# FPGA_S7.net
KiCad netlist of a schematic drawn in EAGLE
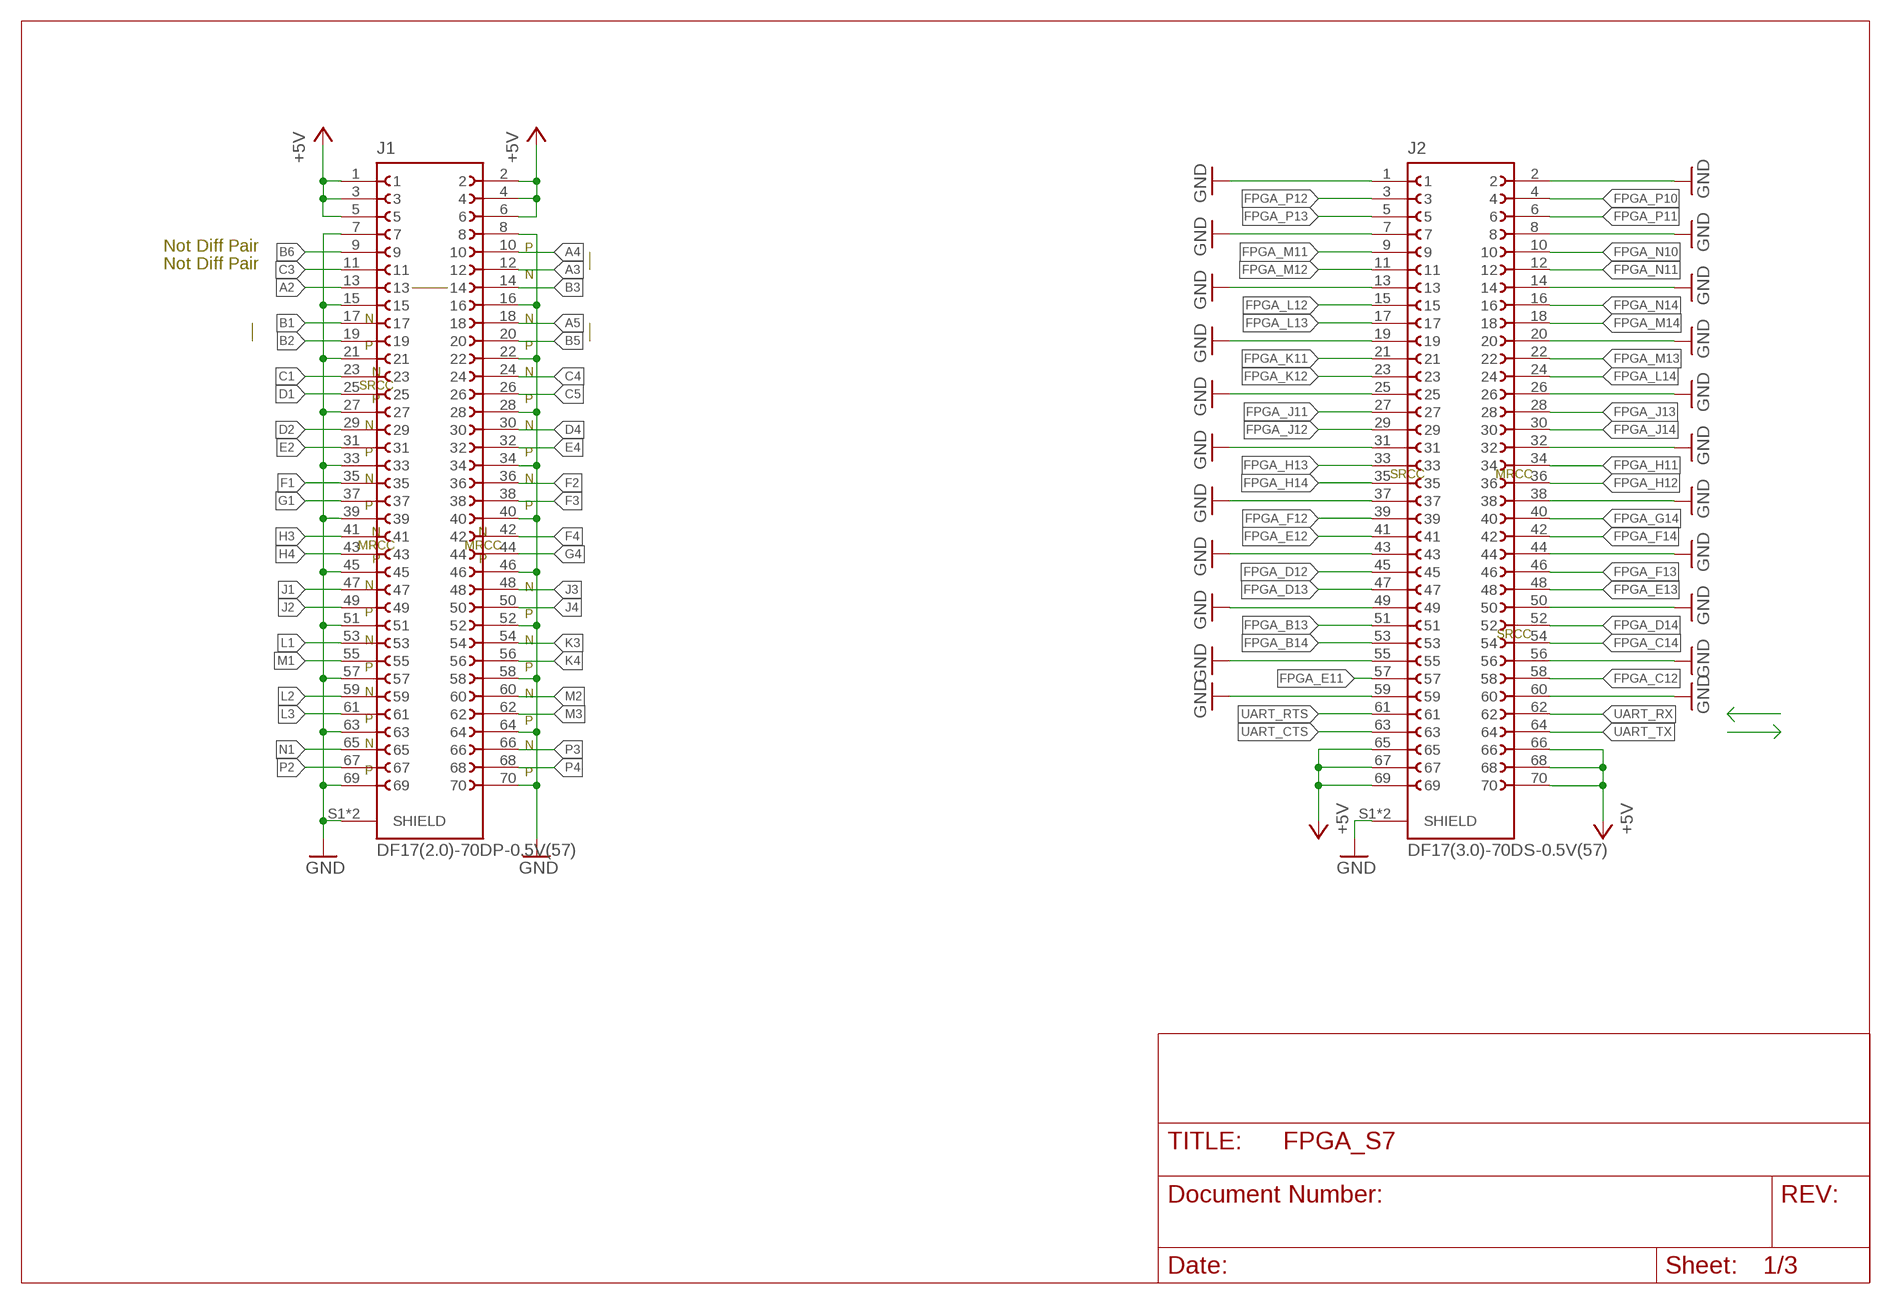
[diagram p0: schematic, sheet 1]
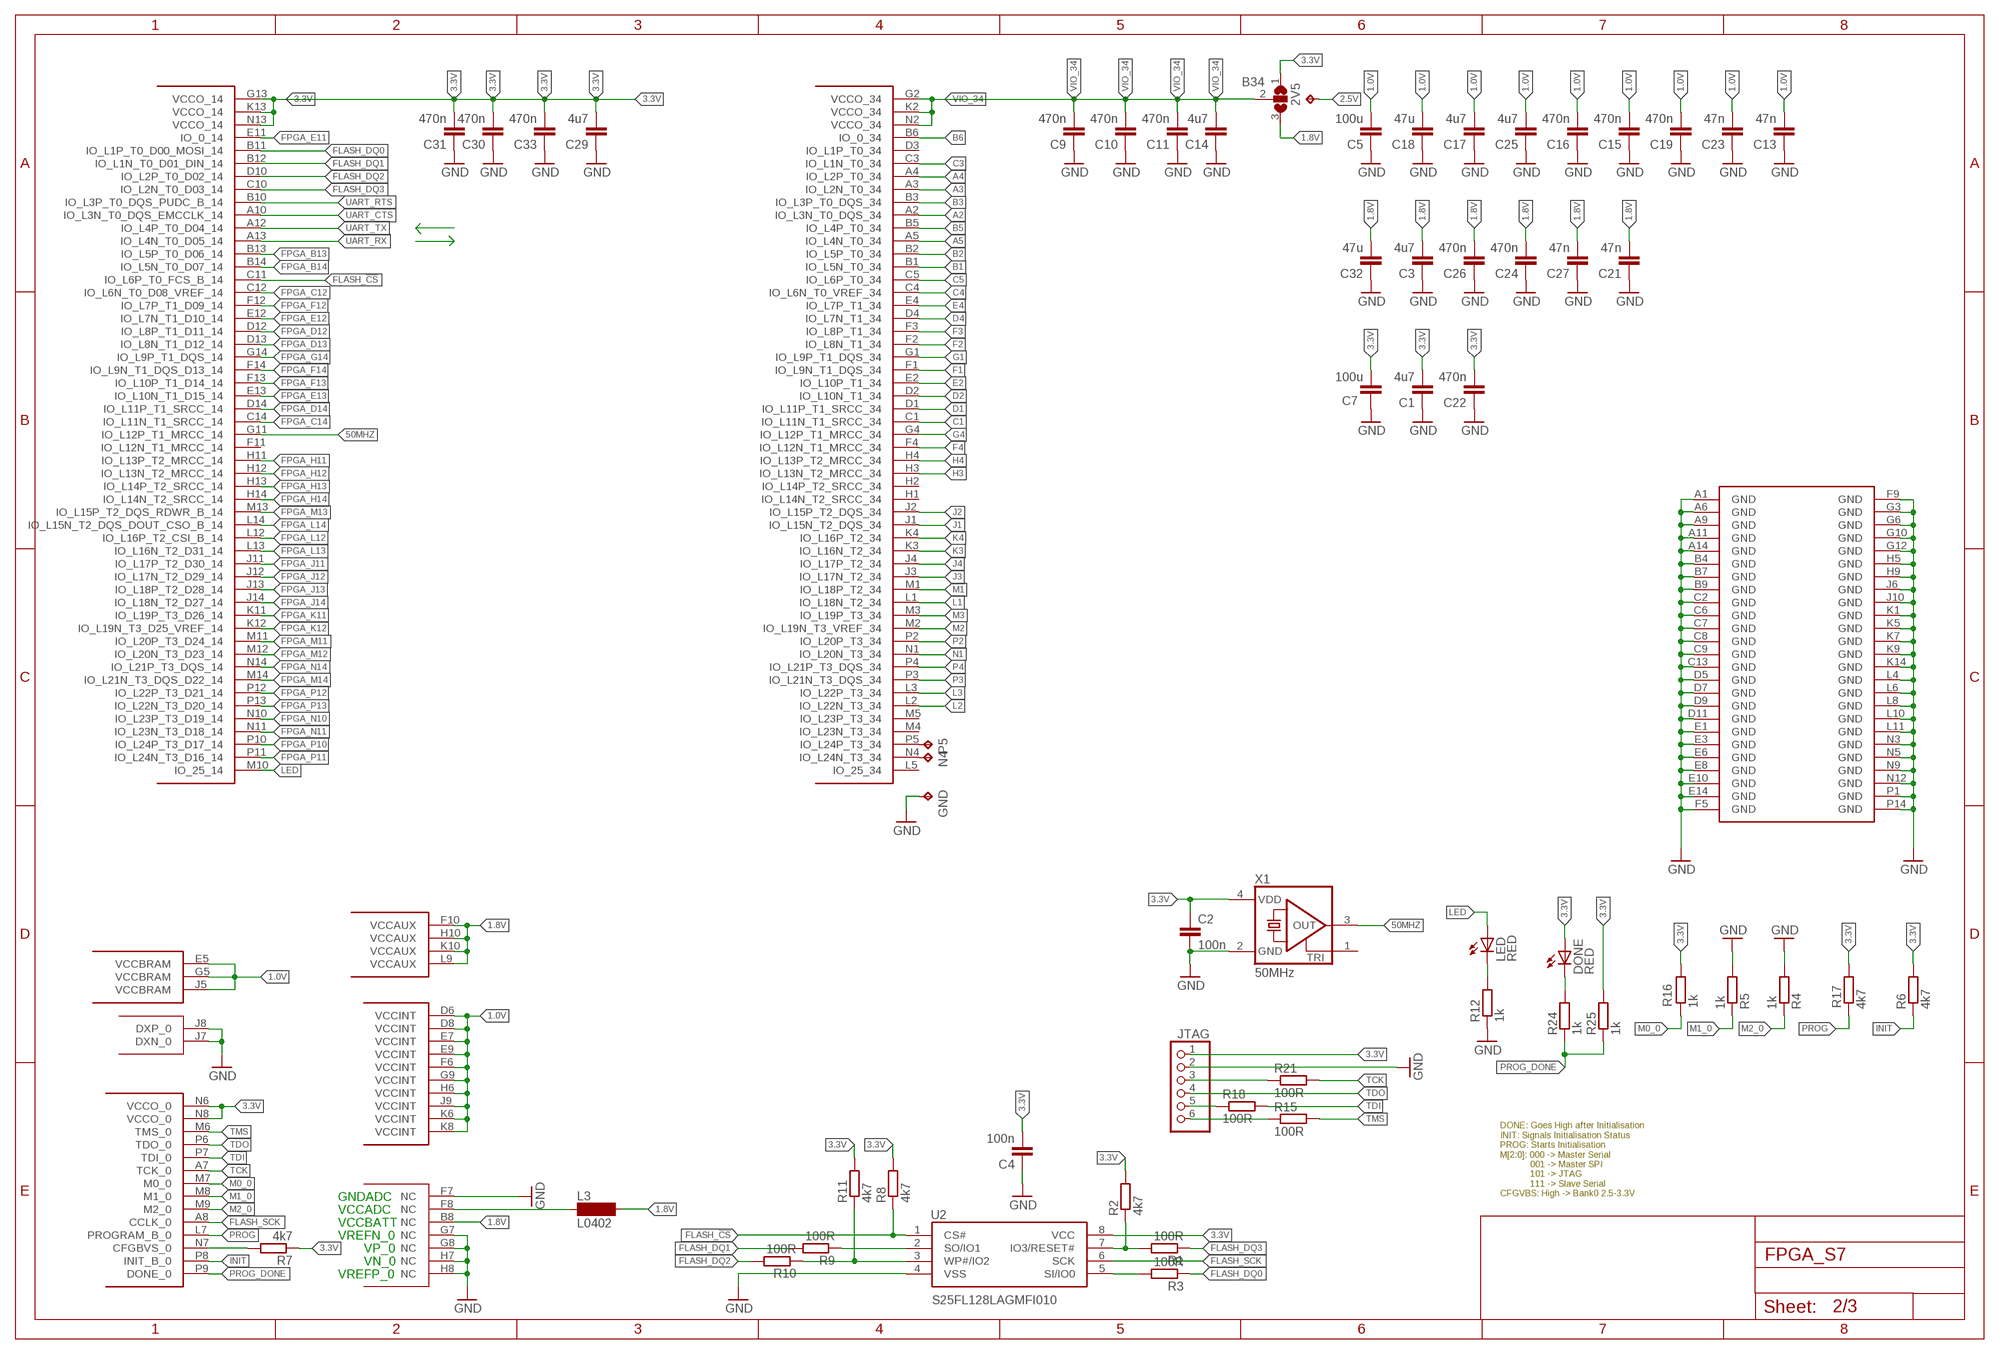
[diagram p1: schematic, sheet 2]
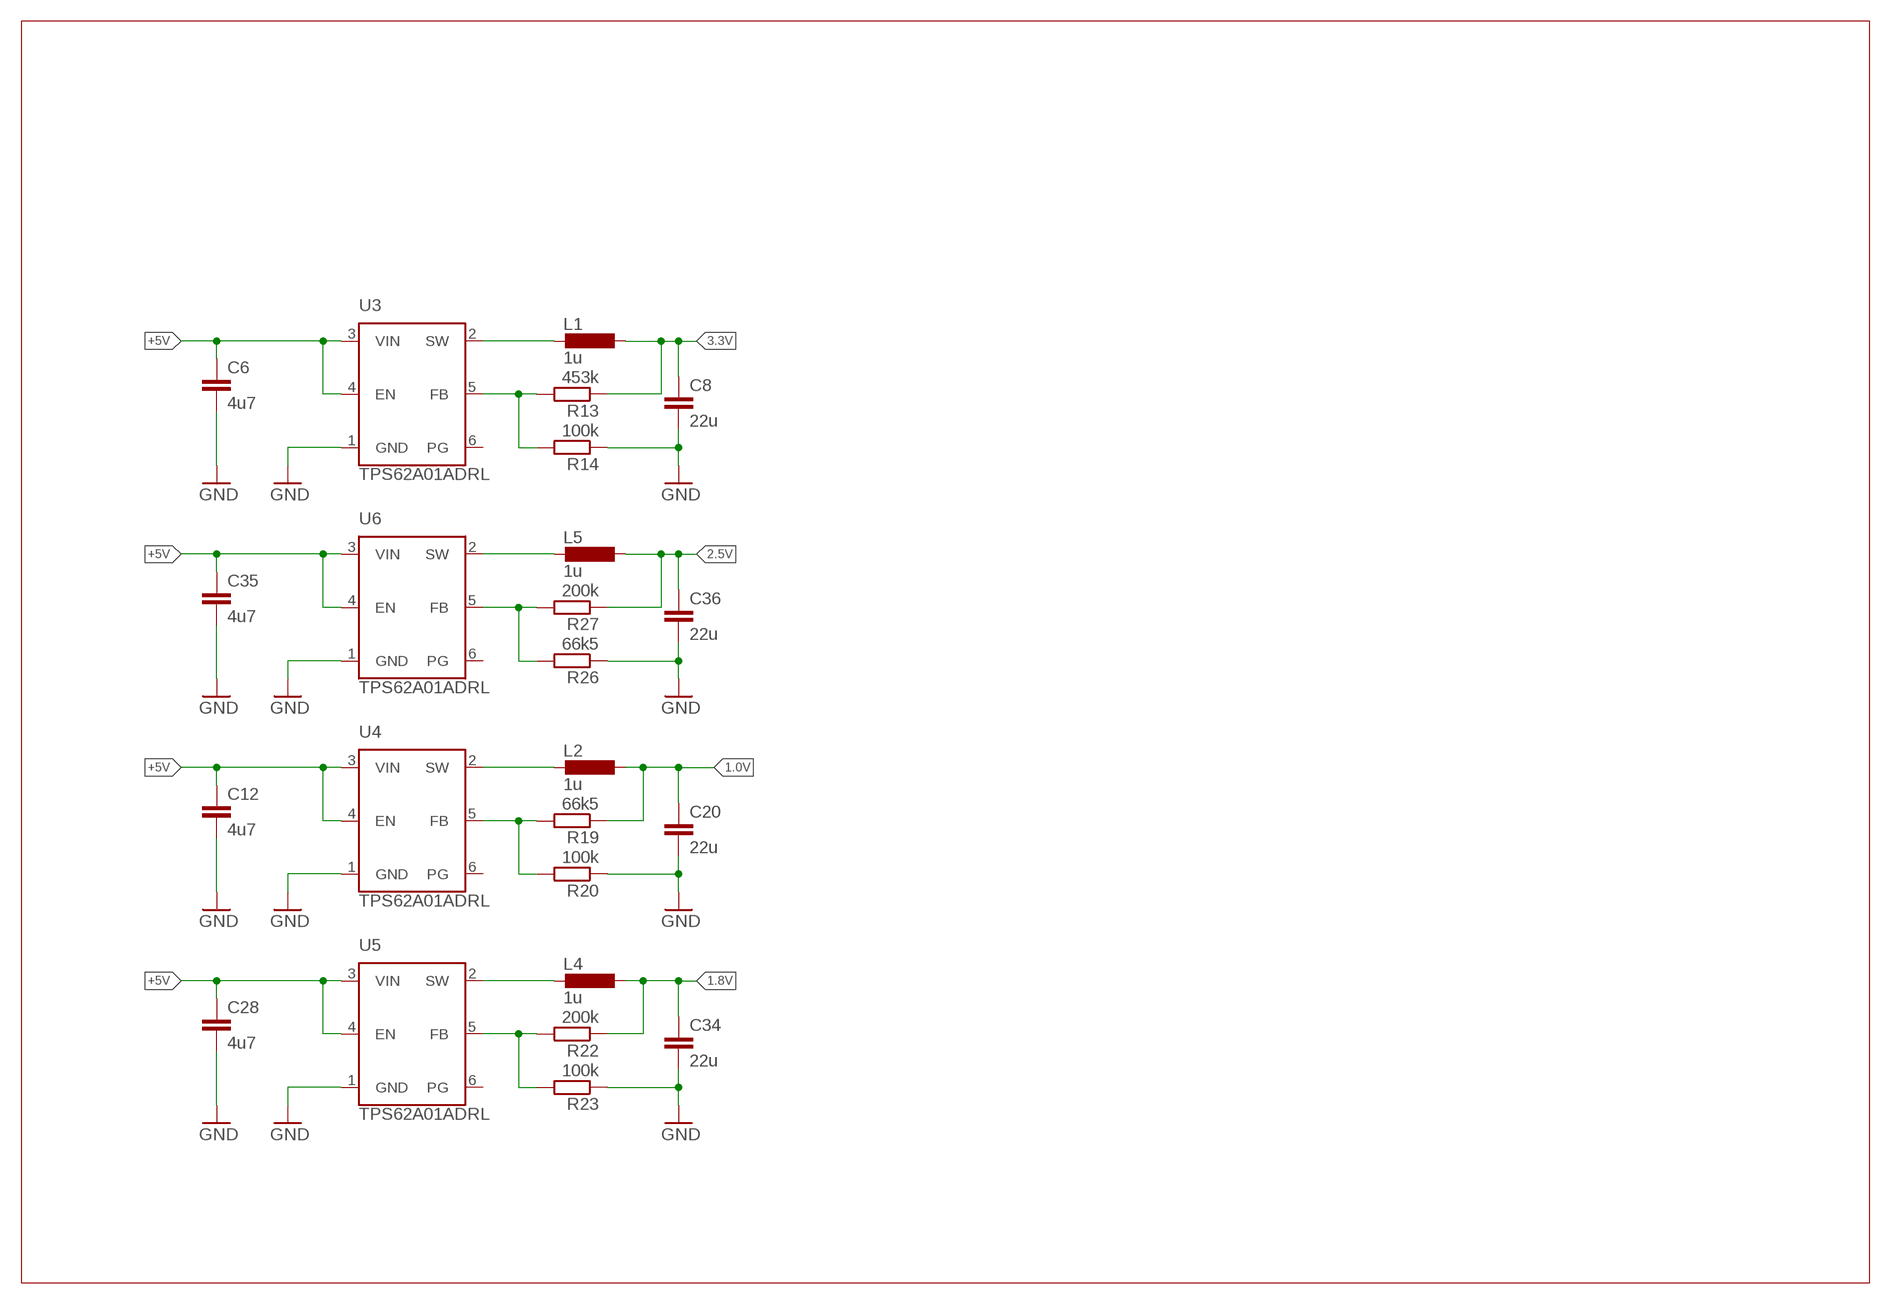
[diagram p2: schematic, sheet 3]

(export (version "E")
  (design (tool "Eeschema 10.0.6"))
  (components
    (comp (ref "2V5")
      (value "TPTP12SQ")
      (footprint "eagle-import:TP12SQ")
      (libsource (lib "eagle-import") (part "TPTP12SQ"))
    )
    (comp (ref "B34")
      (value "SJ2W")
      (footprint "eagle-import:SJ_2")
      (libsource (lib "eagle-import") (part "SJ2W"))
    )
    (comp (ref "C1")
      (value "4u7")
      (footprint "eagle-import:C0603")
      (libsource (lib "eagle-import") (part "C-EUC0603"))
    )
    (comp (ref "C2")
      (value "100n")
      (footprint "eagle-import:C0402")
      (libsource (lib "eagle-import") (part "C-EUC0402"))
    )
    (comp (ref "C3")
      (value "4u7")
      (footprint "eagle-import:C0603")
      (libsource (lib "eagle-import") (part "C-EUC0603"))
    )
    (comp (ref "C4")
      (value "100n")
      (footprint "eagle-import:C0402")
      (libsource (lib "eagle-import") (part "C-EUC0402"))
    )
    (comp (ref "C5")
      (value "100u")
      (footprint "eagle-import:C1206")
      (libsource (lib "eagle-import") (part "rcl_334_C-EUC1206"))
    )
    (comp (ref "C7")
      (value "100u")
      (footprint "eagle-import:C1206")
      (libsource (lib "eagle-import") (part "rcl_334_C-EUC1206"))
    )
    (comp (ref "C9")
      (value "470n")
      (footprint "eagle-import:C0402")
      (libsource (lib "eagle-import") (part "C-EUC0402"))
    )
    (comp (ref "C10")
      (value "470n")
      (footprint "eagle-import:C0402")
      (libsource (lib "eagle-import") (part "C-EUC0402"))
    )
    (comp (ref "C11")
      (value "470n")
      (footprint "eagle-import:C0402")
      (libsource (lib "eagle-import") (part "C-EUC0402"))
    )
    (comp (ref "C13")
      (value "47n")
      (footprint "eagle-import:C0402")
      (libsource (lib "eagle-import") (part "C-EUC0402"))
    )
    (comp (ref "C14")
      (value "4u7")
      (footprint "eagle-import:C0603")
      (libsource (lib "eagle-import") (part "C-EUC0603"))
    )
    (comp (ref "C15")
      (value "470n")
      (footprint "eagle-import:C0402")
      (libsource (lib "eagle-import") (part "C-EUC0402"))
    )
    (comp (ref "C16")
      (value "470n")
      (footprint "eagle-import:C0402")
      (libsource (lib "eagle-import") (part "C-EUC0402"))
    )
    (comp (ref "C17")
      (value "4u7")
      (footprint "eagle-import:C0603")
      (libsource (lib "eagle-import") (part "C-EUC0603"))
    )
    (comp (ref "C18")
      (value "47u")
      (footprint "eagle-import:C0805")
      (libsource (lib "eagle-import") (part "rcl_334_C-EUC0805"))
    )
    (comp (ref "C19")
      (value "470n")
      (footprint "eagle-import:C0402")
      (libsource (lib "eagle-import") (part "C-EUC0402"))
    )
    (comp (ref "C21")
      (value "47n")
      (footprint "eagle-import:C0402")
      (libsource (lib "eagle-import") (part "C-EUC0402"))
    )
    (comp (ref "C22")
      (value "470n")
      (footprint "eagle-import:C0402")
      (libsource (lib "eagle-import") (part "C-EUC0402"))
    )
    (comp (ref "C23")
      (value "47n")
      (footprint "eagle-import:C0402")
      (libsource (lib "eagle-import") (part "C-EUC0402"))
    )
    (comp (ref "C24")
      (value "470n")
      (footprint "eagle-import:C0402")
      (libsource (lib "eagle-import") (part "C-EUC0402"))
    )
    (comp (ref "C25")
      (value "4u7")
      (footprint "eagle-import:C0603")
      (libsource (lib "eagle-import") (part "C-EUC0603"))
    )
    (comp (ref "C26")
      (value "470n")
      (footprint "eagle-import:C0402")
      (libsource (lib "eagle-import") (part "C-EUC0402"))
    )
    (comp (ref "C27")
      (value "47n")
      (footprint "eagle-import:C0402")
      (libsource (lib "eagle-import") (part "C-EUC0402"))
    )
    (comp (ref "C29")
      (value "4u7")
      (footprint "eagle-import:C0603")
      (libsource (lib "eagle-import") (part "C-EUC0603"))
    )
    (comp (ref "C30")
      (value "470n")
      (footprint "eagle-import:C0402")
      (libsource (lib "eagle-import") (part "C-EUC0402"))
    )
    (comp (ref "C31")
      (value "470n")
      (footprint "eagle-import:C0402")
      (libsource (lib "eagle-import") (part "C-EUC0402"))
    )
    (comp (ref "C32")
      (value "47u")
      (footprint "eagle-import:C0805")
      (libsource (lib "eagle-import") (part "C-EUC0805"))
    )
    (comp (ref "C33")
      (value "470n")
      (footprint "eagle-import:C0402")
      (libsource (lib "eagle-import") (part "C-EUC0402"))
    )
    (comp (ref "DONE")
      (value "RED")
      (footprint "eagle-import:CHIP-LED0603")
      (libsource (lib "eagle-import") (part "LEDCHIP-LED0603"))
    )
    (comp (ref "GND")
      (value "TPTP15R")
      (footprint "eagle-import:TP15R")
      (libsource (lib "eagle-import") (part "TPTP15R"))
    )
    (comp (ref "JTAG")
      (value "PINHD-1X6_2.00")
      (footprint "eagle-import:1X06M")
      (libsource (lib "eagle-import") (part "PINHD-1X6_2.00"))
    )
    (comp (ref "L3")
      (value "L0402")
      (footprint "eagle-import:C0402")
      (libsource (lib "eagle-import") (part "L0402"))
    )
    (comp (ref "LED")
      (value "RED")
      (footprint "eagle-import:CHIP-LED0603")
      (libsource (lib "eagle-import") (part "LEDCHIP-LED0603"))
    )
    (comp (ref "N4")
      (value "TPTP15R")
      (footprint "eagle-import:TP15R")
      (libsource (lib "eagle-import") (part "TPTP15R"))
    )
    (comp (ref "P5")
      (value "TPTP15R")
      (footprint "eagle-import:TP15R")
      (libsource (lib "eagle-import") (part "TPTP15R"))
    )
    (comp (ref "R1")
      (value "100R")
      (footprint "eagle-import:R0402")
      (libsource (lib "eagle-import") (part "R-EU_R0402"))
    )
    (comp (ref "R2")
      (value "4k7")
      (footprint "eagle-import:R0402")
      (libsource (lib "eagle-import") (part "R-EU_R0402"))
    )
    (comp (ref "R3")
      (value "100R")
      (footprint "eagle-import:R0402")
      (libsource (lib "eagle-import") (part "R-EU_R0402"))
    )
    (comp (ref "R4")
      (value "1k")
      (footprint "eagle-import:R0402")
      (libsource (lib "eagle-import") (part "R-EU_R0402"))
    )
    (comp (ref "R5")
      (value "1k")
      (footprint "eagle-import:R0402")
      (libsource (lib "eagle-import") (part "R-EU_R0402"))
    )
    (comp (ref "R6")
      (value "4k7")
      (footprint "eagle-import:R0402")
      (libsource (lib "eagle-import") (part "R-EU_R0402"))
    )
    (comp (ref "R7")
      (value "4k7")
      (footprint "eagle-import:R0402")
      (libsource (lib "eagle-import") (part "R-EU_R0402"))
    )
    (comp (ref "R8")
      (value "4k7")
      (footprint "eagle-import:R0402")
      (libsource (lib "eagle-import") (part "R-EU_R0402"))
    )
    (comp (ref "R9")
      (value "100R")
      (footprint "eagle-import:R0402")
      (libsource (lib "eagle-import") (part "R-EU_R0402"))
    )
    (comp (ref "R10")
      (value "100R")
      (footprint "eagle-import:R0402")
      (libsource (lib "eagle-import") (part "R-EU_R0402"))
    )
    (comp (ref "R11")
      (value "4k7")
      (footprint "eagle-import:R0402")
      (libsource (lib "eagle-import") (part "R-EU_R0402"))
    )
    (comp (ref "R12")
      (value "1k")
      (footprint "eagle-import:R0402")
      (libsource (lib "eagle-import") (part "R-EU_R0402"))
    )
    (comp (ref "R15")
      (value "100R")
      (footprint "eagle-import:R0402")
      (libsource (lib "eagle-import") (part "R-EU_R0402"))
    )
    (comp (ref "R16")
      (value "1k")
      (footprint "eagle-import:R0402")
      (libsource (lib "eagle-import") (part "R-EU_R0402"))
    )
    (comp (ref "R17")
      (value "4k7")
      (footprint "eagle-import:R0402")
      (libsource (lib "eagle-import") (part "R-EU_R0402"))
    )
    (comp (ref "R18")
      (value "100R")
      (footprint "eagle-import:R0402")
      (libsource (lib "eagle-import") (part "R-EU_R0402"))
    )
    (comp (ref "R21")
      (value "100R")
      (footprint "eagle-import:R0402")
      (libsource (lib "eagle-import") (part "R-EU_R0402"))
    )
    (comp (ref "R24")
      (value "1k")
      (footprint "eagle-import:R0402")
      (libsource (lib "eagle-import") (part "R-EU_R0402"))
    )
    (comp (ref "R25")
      (value "1k")
      (footprint "eagle-import:R0402")
      (libsource (lib "eagle-import") (part "R-EU_R0402"))
    )
    (comp (ref "U1")
      (value "XC7S15-2FTGB196I")
      (footprint "eagle-import:BGA196C100P14X14_1500X1500X155")
      (fields
        (field (name "DIGIKEY") "122-2233-ND")
        (field (name "PREIS") "28,63")
        (field (name "LCSC") "C1521909")
      )
      (libsource (lib "eagle-import") (part "XC7S15-2FTGB196I"))
    )
    (comp (ref "U2")
      (value "S25FL128LAGMFI010")
      (footprint "eagle-import:SOIC127P800X216-8N")
      (fields (field (name "MOUSER_PART_NUMBER") "727-S25FL128LAGMFI01"))
      (libsource (lib "eagle-import") (part "S25FL128LAGMFI010"))
    )
    (comp (ref "X1")
      (value "50MHz")
      (footprint "eagle-import:ASE")
      (libsource (lib "eagle-import") (part "ASE"))
    )
    (comp (ref "J1")
      (value "DF17(2.0)-70DP-0.5V(57)")
      (footprint "eagle-import:DF17(2.0)-70DP-0.5V(57)")
      (libsource (lib "eagle-import") (part "DF17(2.0)-70DP-0.5V(57)"))
    )
    (comp (ref "J2")
      (value "DF17(3.0)-70DS-0.5V(57)")
      (footprint "eagle-import:DF17(3.0)-70DS-0.5V(57)")
      (libsource (lib "eagle-import") (part "DF17(3.0)-70DS-0.5V(57)"))
    )
    (comp (ref "C6")
      (value "4u7")
      (footprint "eagle-import:C0603")
      (libsource (lib "eagle-import") (part "C-EUC0603"))
    )
    (comp (ref "C8")
      (value "22u")
      (footprint "eagle-import:C0603")
      (libsource (lib "eagle-import") (part "C-EUC0603"))
    )
    (comp (ref "C12")
      (value "4u7")
      (footprint "eagle-import:C0603")
      (libsource (lib "eagle-import") (part "C-EUC0603"))
    )
    (comp (ref "C20")
      (value "22u")
      (footprint "eagle-import:C0603")
      (libsource (lib "eagle-import") (part "C-EUC0603"))
    )
    (comp (ref "C28")
      (value "4u7")
      (footprint "eagle-import:C0603")
      (libsource (lib "eagle-import") (part "C-EUC0603"))
    )
    (comp (ref "C34")
      (value "22u")
      (footprint "eagle-import:C0603")
      (libsource (lib "eagle-import") (part "C-EUC0603"))
    )
    (comp (ref "C35")
      (value "4u7")
      (footprint "eagle-import:C0603")
      (libsource (lib "eagle-import") (part "C-EUC0603"))
    )
    (comp (ref "C36")
      (value "22u")
      (footprint "eagle-import:C0603")
      (libsource (lib "eagle-import") (part "C-EUC0603"))
    )
    (comp (ref "L1")
      (value "1u")
      (footprint "eagle-import:L1008")
      (fields (field (name "MPN") "LQM2HPN1R0MG0L"))
      (libsource (lib "eagle-import") (part "L-EU1008"))
    )
    (comp (ref "L2")
      (value "1u")
      (footprint "eagle-import:L1008")
      (fields (field (name "MPN") "LQM2HPN1R0MG0L"))
      (libsource (lib "eagle-import") (part "L-EU1008"))
    )
    (comp (ref "L4")
      (value "1u")
      (footprint "eagle-import:L1008")
      (fields (field (name "MPN") "LQM2HPN1R0MG0L"))
      (libsource (lib "eagle-import") (part "L-EU1008"))
    )
    (comp (ref "L5")
      (value "1u")
      (footprint "eagle-import:L1008")
      (fields (field (name "MPN") "LQM2HPN1R0MG0L"))
      (libsource (lib "eagle-import") (part "L-EU1008"))
    )
    (comp (ref "R13")
      (value "453k")
      (footprint "eagle-import:R0402")
      (libsource (lib "eagle-import") (part "rcl_334_R-EU_R0402"))
    )
    (comp (ref "R14")
      (value "100k")
      (footprint "eagle-import:R0402")
      (libsource (lib "eagle-import") (part "rcl_334_R-EU_R0402"))
    )
    (comp (ref "R19")
      (value "66k5")
      (footprint "eagle-import:R0402")
      (libsource (lib "eagle-import") (part "rcl_334_R-EU_R0402"))
    )
    (comp (ref "R20")
      (value "100k")
      (footprint "eagle-import:R0402")
      (libsource (lib "eagle-import") (part "rcl_334_R-EU_R0402"))
    )
    (comp (ref "R22")
      (value "200k")
      (footprint "eagle-import:R0402")
      (libsource (lib "eagle-import") (part "rcl_334_R-EU_R0402"))
    )
    (comp (ref "R23")
      (value "100k")
      (footprint "eagle-import:R0402")
      (libsource (lib "eagle-import") (part "rcl_334_R-EU_R0402"))
    )
    (comp (ref "R26")
      (value "66k5")
      (footprint "eagle-import:R0402")
      (libsource (lib "eagle-import") (part "rcl_334_R-EU_R0402"))
    )
    (comp (ref "R27")
      (value "200k")
      (footprint "eagle-import:R0402")
      (libsource (lib "eagle-import") (part "rcl_334_R-EU_R0402"))
    )
    (comp (ref "U3")
      (value "TPS62A01ADRL")
      (footprint "eagle-import:SOTFL50P160X60-6N")
      (fields (field (name "MANUFACTURER_PART_NUMBER") "TPS62A01ADRLR"))
      (libsource (lib "eagle-import") (part "TPS62A01ADRL"))
    )
    (comp (ref "U4")
      (value "TPS62A01ADRL")
      (footprint "eagle-import:SOTFL50P160X60-6N")
      (fields (field (name "MANUFACTURER_PART_NUMBER") "TPS62A01ADRLR"))
      (libsource (lib "eagle-import") (part "TPS62A01ADRL"))
    )
    (comp (ref "U5")
      (value "TPS62A01ADRL")
      (footprint "eagle-import:SOTFL50P160X60-6N")
      (fields (field (name "MANUFACTURER_PART_NUMBER") "TPS62A01ADRLR"))
      (libsource (lib "eagle-import") (part "TPS62A01ADRL"))
    )
    (comp (ref "U6")
      (value "TPS62A01ADRL")
      (footprint "eagle-import:SOTFL50P160X60-6N")
      (fields (field (name "MANUFACTURER_PART_NUMBER") "TPS62A01ADRLR"))
      (libsource (lib "eagle-import") (part "TPS62A01ADRL"))
    )
  )
  (nets
    (net (code "1") (name "+5V") (class "Default")
      (node (ref "C12") (pin "1") (pinfunction "1_1") (pintype "passive"))
      (node (ref "C28") (pin "1") (pinfunction "1_1") (pintype "passive"))
      (node (ref "C35") (pin "1") (pinfunction "1_1") (pintype "passive"))
      (node (ref "C6") (pin "1") (pinfunction "1_1") (pintype "passive"))
      (node (ref "J1") (pin "1") (pinfunction "1_1") (pintype "passive"))
      (node (ref "J1") (pin "2") (pinfunction "2_2") (pintype "passive"))
      (node (ref "J1") (pin "3") (pinfunction "3_3") (pintype "passive"))
      (node (ref "J1") (pin "4") (pinfunction "4_4") (pintype "passive"))
      (node (ref "J1") (pin "5") (pinfunction "5_5") (pintype "passive"))
      (node (ref "J1") (pin "6") (pinfunction "6_6") (pintype "passive"))
      (node (ref "J2") (pin "65") (pinfunction "65_65") (pintype "passive"))
      (node (ref "J2") (pin "66") (pinfunction "66_66") (pintype "passive"))
      (node (ref "J2") (pin "67") (pinfunction "67_67") (pintype "passive"))
      (node (ref "J2") (pin "68") (pinfunction "68_68") (pintype "passive"))
      (node (ref "J2") (pin "69") (pinfunction "69_69") (pintype "passive"))
      (node (ref "J2") (pin "70") (pinfunction "70_70") (pintype "passive"))
      (node (ref "U3") (pin "3") (pinfunction "VIN_3") (pintype "bidirectional"))
      (node (ref "U3") (pin "4") (pinfunction "EN_4") (pintype "bidirectional"))
      (node (ref "U4") (pin "3") (pinfunction "VIN_3") (pintype "bidirectional"))
      (node (ref "U4") (pin "4") (pinfunction "EN_4") (pintype "bidirectional"))
      (node (ref "U5") (pin "3") (pinfunction "VIN_3") (pintype "bidirectional"))
      (node (ref "U5") (pin "4") (pinfunction "EN_4") (pintype "bidirectional"))
      (node (ref "U6") (pin "3") (pinfunction "VIN_3") (pintype "bidirectional"))
      (node (ref "U6") (pin "4") (pinfunction "EN_4") (pintype "bidirectional"))
    )
    (net (code "2") (name "1.0V") (class "Default")
      (node (ref "C13") (pin "2") (pinfunction "2_2") (pintype "passive"))
      (node (ref "C15") (pin "2") (pinfunction "2_2") (pintype "passive"))
      (node (ref "C16") (pin "2") (pinfunction "2_2") (pintype "passive"))
      (node (ref "C17") (pin "2") (pinfunction "2_2") (pintype "passive"))
      (node (ref "C18") (pin "1") (pinfunction "1_1") (pintype "passive"))
      (node (ref "C19") (pin "2") (pinfunction "2_2") (pintype "passive"))
      (node (ref "C20") (pin "1") (pinfunction "1_1") (pintype "passive"))
      (node (ref "C23") (pin "2") (pinfunction "2_2") (pintype "passive"))
      (node (ref "C25") (pin "2") (pinfunction "2_2") (pintype "passive"))
      (node (ref "C5") (pin "1") (pinfunction "1_1") (pintype "passive"))
      (node (ref "L2") (pin "1") (pinfunction "1_1") (pintype "passive"))
      (node (ref "R19") (pin "1") (pinfunction "1_1") (pintype "passive"))
      (node (ref "U1") (pin "D6") (pinfunction "VCCINT_D6") (pintype "bidirectional"))
      (node (ref "U1") (pin "D8") (pinfunction "VCCINT_D8") (pintype "bidirectional"))
      (node (ref "U1") (pin "E5") (pinfunction "VCCBRAM_E5") (pintype "power_in"))
      (node (ref "U1") (pin "E7") (pinfunction "VCCINT_E7") (pintype "bidirectional"))
      (node (ref "U1") (pin "E9") (pinfunction "VCCINT_E9") (pintype "bidirectional"))
      (node (ref "U1") (pin "F6") (pinfunction "VCCINT_F6") (pintype "bidirectional"))
      (node (ref "U1") (pin "G5") (pinfunction "VCCBRAM_G5") (pintype "power_in"))
      (node (ref "U1") (pin "G9") (pinfunction "VCCINT_G9") (pintype "bidirectional"))
      (node (ref "U1") (pin "H6") (pinfunction "VCCINT_H6") (pintype "bidirectional"))
      (node (ref "U1") (pin "J5") (pinfunction "VCCBRAM_J5") (pintype "power_in"))
      (node (ref "U1") (pin "J9") (pinfunction "VCCINT_J9") (pintype "bidirectional"))
      (node (ref "U1") (pin "K6") (pinfunction "VCCINT_K6") (pintype "bidirectional"))
      (node (ref "U1") (pin "K8") (pinfunction "VCCINT_K8") (pintype "bidirectional"))
    )
    (net (code "3") (name "1.8V") (class "Default")
      (node (ref "B34") (pin "3") (pinfunction "3_3") (pintype "passive"))
      (node (ref "C21") (pin "2") (pinfunction "2_2") (pintype "passive"))
      (node (ref "C24") (pin "2") (pinfunction "2_2") (pintype "passive"))
      (node (ref "C26") (pin "2") (pinfunction "2_2") (pintype "passive"))
      (node (ref "C27") (pin "2") (pinfunction "2_2") (pintype "passive"))
      (node (ref "C3") (pin "2") (pinfunction "2_2") (pintype "passive"))
      (node (ref "C32") (pin "2") (pinfunction "2_2") (pintype "passive"))
      (node (ref "C34") (pin "1") (pinfunction "1_1") (pintype "passive"))
      (node (ref "L3") (pin "2") (pinfunction "2_2") (pintype "passive"))
      (node (ref "L4") (pin "1") (pinfunction "1_1") (pintype "passive"))
      (node (ref "R22") (pin "1") (pinfunction "1_1") (pintype "passive"))
      (node (ref "U1") (pin "B8") (pinfunction "NC_B8") (pintype "bidirectional"))
      (node (ref "U1") (pin "F10") (pinfunction "VCCAUX_F10") (pintype "power_in"))
      (node (ref "U1") (pin "H10") (pinfunction "VCCAUX_H10") (pintype "power_in"))
      (node (ref "U1") (pin "K10") (pinfunction "VCCAUX_K10") (pintype "power_in"))
      (node (ref "U1") (pin "L9") (pinfunction "VCCAUX_L9") (pintype "power_in"))
    )
    (net (code "4") (name "2.5V") (class "Default")
      (node (ref "2V5") (pin "TP") (pinfunction "TP_TP") (pintype "input"))
      (node (ref "C36") (pin "1") (pinfunction "1_1") (pintype "passive"))
      (node (ref "L5") (pin "1") (pinfunction "1_1") (pintype "passive"))
      (node (ref "R27") (pin "1") (pinfunction "1_1") (pintype "passive"))
    )
    (net (code "5") (name "3.3V") (class "Default")
      (node (ref "B34") (pin "1") (pinfunction "1_1") (pintype "passive"))
      (node (ref "C1") (pin "2") (pinfunction "2_2") (pintype "passive"))
      (node (ref "C2") (pin "1") (pinfunction "1_1") (pintype "passive"))
      (node (ref "C22") (pin "2") (pinfunction "2_2") (pintype "passive"))
      (node (ref "C29") (pin "2") (pinfunction "2_2") (pintype "passive"))
      (node (ref "C30") (pin "2") (pinfunction "2_2") (pintype "passive"))
      (node (ref "C31") (pin "2") (pinfunction "2_2") (pintype "passive"))
      (node (ref "C33") (pin "2") (pinfunction "2_2") (pintype "passive"))
      (node (ref "C4") (pin "2") (pinfunction "2_2") (pintype "passive"))
      (node (ref "C7") (pin "1") (pinfunction "1_1") (pintype "passive"))
      (node (ref "C8") (pin "1") (pinfunction "1_1") (pintype "passive"))
      (node (ref "DONE") (pin "A") (pinfunction "A_A") (pintype "passive"))
      (node (ref "JTAG") (pin "1") (pinfunction "1_1") (pintype "passive"))
      (node (ref "L1") (pin "1") (pinfunction "1_1") (pintype "passive"))
      (node (ref "R11") (pin "2") (pinfunction "2_2") (pintype "passive"))
      (node (ref "R13") (pin "1") (pinfunction "1_1") (pintype "passive"))
      (node (ref "R16") (pin "1") (pinfunction "1_1") (pintype "passive"))
      (node (ref "R17") (pin "1") (pinfunction "1_1") (pintype "passive"))
      (node (ref "R2") (pin "2") (pinfunction "2_2") (pintype "passive"))
      (node (ref "R25") (pin "2") (pinfunction "2_2") (pintype "passive"))
      (node (ref "R6") (pin "2") (pinfunction "2_2") (pintype "passive"))
      (node (ref "R7") (pin "1") (pinfunction "1_1") (pintype "passive"))
      (node (ref "R8") (pin "2") (pinfunction "2_2") (pintype "passive"))
      (node (ref "U1") (pin "G13") (pinfunction "VCCO_14_G13") (pintype "bidirectional"))
      (node (ref "U1") (pin "K13") (pinfunction "VCCO_14_K13") (pintype "bidirectional"))
      (node (ref "U1") (pin "N13") (pinfunction "VCCO_14_N13") (pintype "bidirectional"))
      (node (ref "U1") (pin "N6") (pinfunction "VCCO_0_N6") (pintype "power_in"))
      (node (ref "U1") (pin "N8") (pinfunction "VCCO_0_N8") (pintype "power_in"))
      (node (ref "U2") (pin "8") (pinfunction "VCC_8") (pintype "bidirectional"))
      (node (ref "X1") (pin "4") (pinfunction "VDD_4") (pintype "power_in"))
    )
    (net (code "6") (name "50MHZ") (class "Default")
      (node (ref "U1") (pin "G11") (pinfunction "IO_L12P_T1_MRCC_14_G11") (pintype "bidirectional"))
      (node (ref "X1") (pin "3") (pinfunction "OUT_3") (pintype "output"))
    )
    (net (code "7") (name "A2") (class "Default")
      (node (ref "J1") (pin "13") (pinfunction "13_13") (pintype "passive"))
      (node (ref "U1") (pin "A2") (pinfunction "IO_L3N_T0_DQS_34_A2") (pintype "bidirectional"))
    )
    (net (code "8") (name "A3") (class "Default")
      (node (ref "J1") (pin "12") (pinfunction "12_12") (pintype "passive"))
      (node (ref "U1") (pin "A3") (pinfunction "IO_L2N_T0_34_A3") (pintype "bidirectional"))
    )
    (net (code "9") (name "A4") (class "Default")
      (node (ref "J1") (pin "10") (pinfunction "10_10") (pintype "passive"))
      (node (ref "U1") (pin "A4") (pinfunction "IO_L2P_T0_34_A4") (pintype "bidirectional"))
    )
    (net (code "10") (name "A5") (class "Default")
      (node (ref "J1") (pin "18") (pinfunction "18_18") (pintype "passive"))
      (node (ref "U1") (pin "A5") (pinfunction "IO_L4N_T0_34_A5") (pintype "bidirectional"))
    )
    (net (code "11") (name "B1") (class "Default")
      (node (ref "J1") (pin "17") (pinfunction "17_17") (pintype "passive"))
      (node (ref "U1") (pin "B1") (pinfunction "IO_L5N_T0_34_B1") (pintype "bidirectional"))
    )
    (net (code "12") (name "B2") (class "Default")
      (node (ref "J1") (pin "19") (pinfunction "19_19") (pintype "passive"))
      (node (ref "U1") (pin "B2") (pinfunction "IO_L5P_T0_34_B2") (pintype "bidirectional"))
    )
    (net (code "13") (name "B3") (class "Default")
      (node (ref "J1") (pin "14") (pinfunction "14_14") (pintype "passive"))
      (node (ref "U1") (pin "B3") (pinfunction "IO_L3P_T0_DQS_34_B3") (pintype "bidirectional"))
    )
    (net (code "14") (name "B5") (class "Default")
      (node (ref "J1") (pin "20") (pinfunction "20_20") (pintype "passive"))
      (node (ref "U1") (pin "B5") (pinfunction "IO_L4P_T0_34_B5") (pintype "bidirectional"))
    )
    (net (code "15") (name "B6") (class "Default")
      (node (ref "J1") (pin "9") (pinfunction "9_9") (pintype "passive"))
      (node (ref "U1") (pin "B6") (pinfunction "IO_0_34_B6") (pintype "bidirectional"))
    )
    (net (code "16") (name "C1") (class "Default")
      (node (ref "J1") (pin "23") (pinfunction "23_23") (pintype "passive"))
      (node (ref "U1") (pin "C1") (pinfunction "IO_L11N_T1_SRCC_34_C1") (pintype "bidirectional"))
    )
    (net (code "17") (name "C3") (class "Default")
      (node (ref "J1") (pin "11") (pinfunction "11_11") (pintype "passive"))
      (node (ref "U1") (pin "C3") (pinfunction "IO_L1N_T0_34_C3") (pintype "bidirectional"))
    )
    (net (code "18") (name "C4") (class "Default")
      (node (ref "J1") (pin "24") (pinfunction "24_24") (pintype "passive"))
      (node (ref "U1") (pin "C4") (pinfunction "IO_L6N_T0_VREF_34_C4") (pintype "bidirectional"))
    )
    (net (code "19") (name "C5") (class "Default")
      (node (ref "J1") (pin "26") (pinfunction "26_26") (pintype "passive"))
      (node (ref "U1") (pin "C5") (pinfunction "IO_L6P_T0_34_C5") (pintype "bidirectional"))
    )
    (net (code "20") (name "D1") (class "Default")
      (node (ref "J1") (pin "25") (pinfunction "25_25") (pintype "passive"))
      (node (ref "U1") (pin "D1") (pinfunction "IO_L11P_T1_SRCC_34_D1") (pintype "bidirectional"))
    )
    (net (code "21") (name "D2") (class "Default")
      (node (ref "J1") (pin "29") (pinfunction "29_29") (pintype "passive"))
      (node (ref "U1") (pin "D2") (pinfunction "IO_L10N_T1_34_D2") (pintype "bidirectional"))
    )
    (net (code "22") (name "D4") (class "Default")
      (node (ref "J1") (pin "30") (pinfunction "30_30") (pintype "passive"))
      (node (ref "U1") (pin "D4") (pinfunction "IO_L7N_T1_34_D4") (pintype "bidirectional"))
    )
    (net (code "23") (name "E2") (class "Default")
      (node (ref "J1") (pin "31") (pinfunction "31_31") (pintype "passive"))
      (node (ref "U1") (pin "E2") (pinfunction "IO_L10P_T1_34_E2") (pintype "bidirectional"))
    )
    (net (code "24") (name "E4") (class "Default")
      (node (ref "J1") (pin "32") (pinfunction "32_32") (pintype "passive"))
      (node (ref "U1") (pin "E4") (pinfunction "IO_L7P_T1_34_E4") (pintype "bidirectional"))
    )
    (net (code "25") (name "F1") (class "Default")
      (node (ref "J1") (pin "35") (pinfunction "35_35") (pintype "passive"))
      (node (ref "U1") (pin "F1") (pinfunction "IO_L9N_T1_DQS_34_F1") (pintype "bidirectional"))
    )
    (net (code "26") (name "F2") (class "Default")
      (node (ref "J1") (pin "36") (pinfunction "36_36") (pintype "passive"))
      (node (ref "U1") (pin "F2") (pinfunction "IO_L8N_T1_34_F2") (pintype "bidirectional"))
    )
    (net (code "27") (name "F3") (class "Default")
      (node (ref "J1") (pin "38") (pinfunction "38_38") (pintype "passive"))
      (node (ref "U1") (pin "F3") (pinfunction "IO_L8P_T1_34_F3") (pintype "bidirectional"))
    )
    (net (code "28") (name "F4") (class "Default")
      (node (ref "J1") (pin "42") (pinfunction "42_42") (pintype "passive"))
      (node (ref "U1") (pin "F4") (pinfunction "IO_L12N_T1_MRCC_34_F4") (pintype "bidirectional"))
    )
    (net (code "29") (name "FLASH_DQ0") (class "Default")
      (node (ref "R3") (pin "1") (pinfunction "1_1") (pintype "passive"))
      (node (ref "U1") (pin "B11") (pinfunction "IO_L1P_T0_D00_MOSI_14_B11") (pintype "bidirectional"))
    )
    (net (code "30") (name "FLASH_DQ1") (class "Default")
      (node (ref "R9") (pin "2") (pinfunction "2_2") (pintype "passive"))
      (node (ref "U1") (pin "B12") (pinfunction "IO_L1N_T0_D01_DIN_14_B12") (pintype "bidirectional"))
    )
    (net (code "31") (name "FLASH_DQ2") (class "Default")
      (node (ref "R10") (pin "2") (pinfunction "2_2") (pintype "passive"))
      (node (ref "U1") (pin "D10") (pinfunction "IO_L2P_T0_D02_14_D10") (pintype "bidirectional"))
    )
    (net (code "32") (name "FLASH_DQ3") (class "Default")
      (node (ref "R1") (pin "1") (pinfunction "1_1") (pintype "passive"))
      (node (ref "U1") (pin "C10") (pinfunction "IO_L2N_T0_D03_14_C10") (pintype "bidirectional"))
    )
    (net (code "33") (name "FLASH_SCK") (class "Default")
      (node (ref "U1") (pin "A8") (pinfunction "CCLK_0_A8") (pintype "bidirectional"))
      (node (ref "U2") (pin "6") (pinfunction "SCK_6") (pintype "bidirectional"))
    )
    (net (code "34") (name "FLASH_~{CS}") (class "Default")
      (node (ref "R8") (pin "1") (pinfunction "1_1") (pintype "passive"))
      (node (ref "U1") (pin "C11") (pinfunction "IO_L6P_T0_FCS_B_14_C11") (pintype "bidirectional"))
      (node (ref "U2") (pin "1") (pinfunction "CS#_1") (pintype "bidirectional"))
    )
    (net (code "35") (name "FPGA_B13") (class "Default")
      (node (ref "J2") (pin "51") (pinfunction "51_51") (pintype "passive"))
      (node (ref "U1") (pin "B13") (pinfunction "IO_L5P_T0_D06_14_B13") (pintype "bidirectional"))
    )
    (net (code "36") (name "FPGA_B14") (class "Default")
      (node (ref "J2") (pin "53") (pinfunction "53_53") (pintype "passive"))
      (node (ref "U1") (pin "B14") (pinfunction "IO_L5N_T0_D07_14_B14") (pintype "bidirectional"))
    )
    (net (code "37") (name "FPGA_C12") (class "Default")
      (node (ref "J2") (pin "58") (pinfunction "58_58") (pintype "passive"))
      (node (ref "U1") (pin "C12") (pinfunction "IO_L6N_T0_D08_VREF_14_C12") (pintype "bidirectional"))
    )
    (net (code "38") (name "FPGA_C14") (class "Default")
      (node (ref "J2") (pin "54") (pinfunction "54_54") (pintype "passive"))
      (node (ref "U1") (pin "C14") (pinfunction "IO_L11N_T1_SRCC_14_C14") (pintype "bidirectional"))
    )
    (net (code "39") (name "FPGA_D12") (class "Default")
      (node (ref "J2") (pin "45") (pinfunction "45_45") (pintype "passive"))
      (node (ref "U1") (pin "D12") (pinfunction "IO_L8P_T1_D11_14_D12") (pintype "bidirectional"))
    )
    (net (code "40") (name "FPGA_D13") (class "Default")
      (node (ref "J2") (pin "47") (pinfunction "47_47") (pintype "passive"))
      (node (ref "U1") (pin "D13") (pinfunction "IO_L8N_T1_D12_14_D13") (pintype "bidirectional"))
    )
    (net (code "41") (name "FPGA_D14") (class "Default")
      (node (ref "J2") (pin "52") (pinfunction "52_52") (pintype "passive"))
      (node (ref "U1") (pin "D14") (pinfunction "IO_L11P_T1_SRCC_14_D14") (pintype "bidirectional"))
    )
    (net (code "42") (name "FPGA_E11") (class "Default")
      (node (ref "J2") (pin "57") (pinfunction "57_57") (pintype "passive"))
      (node (ref "U1") (pin "E11") (pinfunction "IO_0_14_E11") (pintype "bidirectional"))
    )
    (net (code "43") (name "FPGA_E12") (class "Default")
      (node (ref "J2") (pin "41") (pinfunction "41_41") (pintype "passive"))
      (node (ref "U1") (pin "E12") (pinfunction "IO_L7N_T1_D10_14_E12") (pintype "bidirectional"))
    )
    (net (code "44") (name "FPGA_E13") (class "Default")
      (node (ref "J2") (pin "48") (pinfunction "48_48") (pintype "passive"))
      (node (ref "U1") (pin "E13") (pinfunction "IO_L10N_T1_D15_14_E13") (pintype "bidirectional"))
    )
    (net (code "45") (name "FPGA_F12") (class "Default")
      (node (ref "J2") (pin "39") (pinfunction "39_39") (pintype "passive"))
      (node (ref "U1") (pin "F12") (pinfunction "IO_L7P_T1_D09_14_F12") (pintype "bidirectional"))
    )
    (net (code "46") (name "FPGA_F13") (class "Default")
      (node (ref "J2") (pin "46") (pinfunction "46_46") (pintype "passive"))
      (node (ref "U1") (pin "F13") (pinfunction "IO_L10P_T1_D14_14_F13") (pintype "bidirectional"))
    )
    (net (code "47") (name "FPGA_F14") (class "Default")
      (node (ref "J2") (pin "42") (pinfunction "42_42") (pintype "passive"))
      (node (ref "U1") (pin "F14") (pinfunction "IO_L9N_T1_DQS_D13_14_F14") (pintype "bidirectional"))
    )
    (net (code "48") (name "FPGA_G14") (class "Default")
      (node (ref "J2") (pin "40") (pinfunction "40_40") (pintype "passive"))
      (node (ref "U1") (pin "G14") (pinfunction "IO_L9P_T1_DQS_14_G14") (pintype "bidirectional"))
    )
    (net (code "49") (name "FPGA_H11") (class "Default")
      (node (ref "J2") (pin "34") (pinfunction "34_34") (pintype "passive"))
      (node (ref "U1") (pin "H11") (pinfunction "IO_L13P_T2_MRCC_14_H11") (pintype "bidirectional"))
    )
    (net (code "50") (name "FPGA_H12") (class "Default")
      (node (ref "J2") (pin "36") (pinfunction "36_36") (pintype "passive"))
      (node (ref "U1") (pin "H12") (pinfunction "IO_L13N_T2_MRCC_14_H12") (pintype "bidirectional"))
    )
    (net (code "51") (name "FPGA_H13") (class "Default")
      (node (ref "J2") (pin "33") (pinfunction "33_33") (pintype "passive"))
      (node (ref "U1") (pin "H13") (pinfunction "IO_L14P_T2_SRCC_14_H13") (pintype "bidirectional"))
    )
    (net (code "52") (name "FPGA_H14") (class "Default")
      (node (ref "J2") (pin "35") (pinfunction "35_35") (pintype "passive"))
      (node (ref "U1") (pin "H14") (pinfunction "IO_L14N_T2_SRCC_14_H14") (pintype "bidirectional"))
    )
    (net (code "53") (name "FPGA_J11") (class "Default")
      (node (ref "J2") (pin "27") (pinfunction "27_27") (pintype "passive"))
      (node (ref "U1") (pin "J11") (pinfunction "IO_L17P_T2_D30_14_J11") (pintype "bidirectional"))
    )
    (net (code "54") (name "FPGA_J12") (class "Default")
      (node (ref "J2") (pin "29") (pinfunction "29_29") (pintype "passive"))
      (node (ref "U1") (pin "J12") (pinfunction "IO_L17N_T2_D29_14_J12") (pintype "bidirectional"))
    )
    (net (code "55") (name "FPGA_J13") (class "Default")
      (node (ref "J2") (pin "28") (pinfunction "28_28") (pintype "passive"))
      (node (ref "U1") (pin "J13") (pinfunction "IO_L18P_T2_D28_14_J13") (pintype "bidirectional"))
    )
    (net (code "56") (name "FPGA_J14") (class "Default")
      (node (ref "J2") (pin "30") (pinfunction "30_30") (pintype "passive"))
      (node (ref "U1") (pin "J14") (pinfunction "IO_L18N_T2_D27_14_J14") (pintype "bidirectional"))
    )
    (net (code "57") (name "FPGA_K11") (class "Default")
      (node (ref "J2") (pin "21") (pinfunction "21_21") (pintype "passive"))
      (node (ref "U1") (pin "K11") (pinfunction "IO_L19P_T3_D26_14_K11") (pintype "bidirectional"))
    )
    (net (code "58") (name "FPGA_K12") (class "Default")
      (node (ref "J2") (pin "23") (pinfunction "23_23") (pintype "passive"))
      (node (ref "U1") (pin "K12") (pinfunction "IO_L19N_T3_D25_VREF_14_K12") (pintype "bidirectional"))
    )
    (net (code "59") (name "FPGA_L12") (class "Default")
      (node (ref "J2") (pin "15") (pinfunction "15_15") (pintype "passive"))
      (node (ref "U1") (pin "L12") (pinfunction "IO_L16P_T2_CSI_B_14_L12") (pintype "bidirectional"))
    )
    (net (code "60") (name "FPGA_L13") (class "Default")
      (node (ref "J2") (pin "17") (pinfunction "17_17") (pintype "passive"))
      (node (ref "U1") (pin "L13") (pinfunction "IO_L16N_T2_D31_14_L13") (pintype "bidirectional"))
    )
    (net (code "61") (name "FPGA_L14") (class "Default")
      (node (ref "J2") (pin "24") (pinfunction "24_24") (pintype "passive"))
      (node (ref "U1") (pin "L14") (pinfunction "IO_L15N_T2_DQS_DOUT_CSO_B_14_L14") (pintype "bidirectional"))
    )
    (net (code "62") (name "FPGA_M11") (class "Default")
      (node (ref "J2") (pin "9") (pinfunction "9_9") (pintype "passive"))
      (node (ref "U1") (pin "M11") (pinfunction "IO_L20P_T3_D24_14_M11") (pintype "bidirectional"))
    )
    (net (code "63") (name "FPGA_M12") (class "Default")
      (node (ref "J2") (pin "11") (pinfunction "11_11") (pintype "passive"))
      (node (ref "U1") (pin "M12") (pinfunction "IO_L20N_T3_D23_14_M12") (pintype "bidirectional"))
    )
    (net (code "64") (name "FPGA_M13") (class "Default")
      (node (ref "J2") (pin "22") (pinfunction "22_22") (pintype "passive"))
      (node (ref "U1") (pin "M13") (pinfunction "IO_L15P_T2_DQS_RDWR_B_14_M13") (pintype "bidirectional"))
    )
    (net (code "65") (name "FPGA_M14") (class "Default")
      (node (ref "J2") (pin "18") (pinfunction "18_18") (pintype "passive"))
      (node (ref "U1") (pin "M14") (pinfunction "IO_L21N_T3_DQS_D22_14_M14") (pintype "bidirectional"))
    )
    (net (code "66") (name "FPGA_N10") (class "Default")
      (node (ref "J2") (pin "10") (pinfunction "10_10") (pintype "passive"))
      (node (ref "U1") (pin "N10") (pinfunction "IO_L23P_T3_D19_14_N10") (pintype "bidirectional"))
    )
    (net (code "67") (name "FPGA_N11") (class "Default")
      (node (ref "J2") (pin "12") (pinfunction "12_12") (pintype "passive"))
      (node (ref "U1") (pin "N11") (pinfunction "IO_L23N_T3_D18_14_N11") (pintype "bidirectional"))
    )
    (net (code "68") (name "FPGA_N14") (class "Default")
      (node (ref "J2") (pin "16") (pinfunction "16_16") (pintype "passive"))
      (node (ref "U1") (pin "N14") (pinfunction "IO_L21P_T3_DQS_14_N14") (pintype "bidirectional"))
    )
    (net (code "69") (name "FPGA_P10") (class "Default")
      (node (ref "J2") (pin "4") (pinfunction "4_4") (pintype "passive"))
      (node (ref "U1") (pin "P10") (pinfunction "IO_L24P_T3_D17_14_P10") (pintype "bidirectional"))
    )
    (net (code "70") (name "FPGA_P11") (class "Default")
      (node (ref "J2") (pin "6") (pinfunction "6_6") (pintype "passive"))
      (node (ref "U1") (pin "P11") (pinfunction "IO_L24N_T3_D16_14_P11") (pintype "bidirectional"))
    )
    (net (code "71") (name "FPGA_P12") (class "Default")
      (node (ref "J2") (pin "3") (pinfunction "3_3") (pintype "passive"))
      (node (ref "U1") (pin "P12") (pinfunction "IO_L22P_T3_D21_14_P12") (pintype "bidirectional"))
    )
    (net (code "72") (name "FPGA_P13") (class "Default")
      (node (ref "J2") (pin "5") (pinfunction "5_5") (pintype "passive"))
      (node (ref "U1") (pin "P13") (pinfunction "IO_L22N_T3_D20_14_P13") (pintype "bidirectional"))
    )
    (net (code "73") (name "G1") (class "Default")
      (node (ref "J1") (pin "37") (pinfunction "37_37") (pintype "passive"))
      (node (ref "U1") (pin "G1") (pinfunction "IO_L9P_T1_DQS_34_G1") (pintype "bidirectional"))
    )
    (net (code "74") (name "G4") (class "Default")
      (node (ref "J1") (pin "44") (pinfunction "44_44") (pintype "passive"))
      (node (ref "U1") (pin "G4") (pinfunction "IO_L12P_T1_MRCC_34_G4") (pintype "bidirectional"))
    )
    (net (code "75") (name "GND") (class "Default")
      (node (ref "C1") (pin "1") (pinfunction "1_1") (pintype "passive"))
      (node (ref "C10") (pin "1") (pinfunction "1_1") (pintype "passive"))
      (node (ref "C11") (pin "1") (pinfunction "1_1") (pintype "passive"))
      (node (ref "C12") (pin "2") (pinfunction "2_2") (pintype "passive"))
      (node (ref "C13") (pin "1") (pinfunction "1_1") (pintype "passive"))
      (node (ref "C14") (pin "1") (pinfunction "1_1") (pintype "passive"))
      (node (ref "C15") (pin "1") (pinfunction "1_1") (pintype "passive"))
      (node (ref "C16") (pin "1") (pinfunction "1_1") (pintype "passive"))
      (node (ref "C17") (pin "1") (pinfunction "1_1") (pintype "passive"))
      (node (ref "C18") (pin "2") (pinfunction "2_2") (pintype "passive"))
      (node (ref "C19") (pin "1") (pinfunction "1_1") (pintype "passive"))
      (node (ref "C2") (pin "2") (pinfunction "2_2") (pintype "passive"))
      (node (ref "C20") (pin "2") (pinfunction "2_2") (pintype "passive"))
      (node (ref "C21") (pin "1") (pinfunction "1_1") (pintype "passive"))
      (node (ref "C22") (pin "1") (pinfunction "1_1") (pintype "passive"))
      (node (ref "C23") (pin "1") (pinfunction "1_1") (pintype "passive"))
      (node (ref "C24") (pin "1") (pinfunction "1_1") (pintype "passive"))
      (node (ref "C25") (pin "1") (pinfunction "1_1") (pintype "passive"))
      (node (ref "C26") (pin "1") (pinfunction "1_1") (pintype "passive"))
      (node (ref "C27") (pin "1") (pinfunction "1_1") (pintype "passive"))
      (node (ref "C28") (pin "2") (pinfunction "2_2") (pintype "passive"))
      (node (ref "C29") (pin "1") (pinfunction "1_1") (pintype "passive"))
      (node (ref "C3") (pin "1") (pinfunction "1_1") (pintype "passive"))
      (node (ref "C30") (pin "1") (pinfunction "1_1") (pintype "passive"))
      (node (ref "C31") (pin "1") (pinfunction "1_1") (pintype "passive"))
      (node (ref "C32") (pin "1") (pinfunction "1_1") (pintype "passive"))
      (node (ref "C33") (pin "1") (pinfunction "1_1") (pintype "passive"))
      (node (ref "C34") (pin "2") (pinfunction "2_2") (pintype "passive"))
      (node (ref "C35") (pin "2") (pinfunction "2_2") (pintype "passive"))
      (node (ref "C36") (pin "2") (pinfunction "2_2") (pintype "passive"))
      (node (ref "C4") (pin "1") (pinfunction "1_1") (pintype "passive"))
      (node (ref "C5") (pin "2") (pinfunction "2_2") (pintype "passive"))
      (node (ref "C6") (pin "2") (pinfunction "2_2") (pintype "passive"))
      (node (ref "C7") (pin "2") (pinfunction "2_2") (pintype "passive"))
      (node (ref "C8") (pin "2") (pinfunction "2_2") (pintype "passive"))
      (node (ref "C9") (pin "1") (pinfunction "1_1") (pintype "passive"))
      (node (ref "GND") (pin "TP") (pinfunction "TP_TP") (pintype "input"))
      (node (ref "J1") (pin "15") (pinfunction "15_15") (pintype "passive"))
      (node (ref "J1") (pin "16") (pinfunction "16_16") (pintype "passive"))
      (node (ref "J1") (pin "21") (pinfunction "21_21") (pintype "passive"))
      (node (ref "J1") (pin "22") (pinfunction "22_22") (pintype "passive"))
      (node (ref "J1") (pin "27") (pinfunction "27_27") (pintype "passive"))
      (node (ref "J1") (pin "28") (pinfunction "28_28") (pintype "passive"))
      (node (ref "J1") (pin "33") (pinfunction "33_33") (pintype "passive"))
      (node (ref "J1") (pin "34") (pinfunction "34_34") (pintype "passive"))
      (node (ref "J1") (pin "39") (pinfunction "39_39") (pintype "passive"))
      (node (ref "J1") (pin "40") (pinfunction "40_40") (pintype "passive"))
      (node (ref "J1") (pin "45") (pinfunction "45_45") (pintype "passive"))
      (node (ref "J1") (pin "46") (pinfunction "46_46") (pintype "passive"))
      (node (ref "J1") (pin "51") (pinfunction "51_51") (pintype "passive"))
      (node (ref "J1") (pin "52") (pinfunction "52_52") (pintype "passive"))
      (node (ref "J1") (pin "57") (pinfunction "57_57") (pintype "passive"))
      (node (ref "J1") (pin "58") (pinfunction "58_58") (pintype "passive"))
      (node (ref "J1") (pin "63") (pinfunction "63_63") (pintype "passive"))
      (node (ref "J1") (pin "64") (pinfunction "64_64") (pintype "passive"))
      (node (ref "J1") (pin "69") (pinfunction "69_69") (pintype "passive"))
      (node (ref "J1") (pin "7") (pinfunction "7_7") (pintype "passive"))
      (node (ref "J1") (pin "70") (pinfunction "70_70") (pintype "passive"))
      (node (ref "J1") (pin "8") (pinfunction "8_8") (pintype "passive"))
      (node (ref "J1") (pin "S1") (pinfunction "SHIELD_S1") (pintype "passive"))
      (node (ref "J1") (pin "S2") (pinfunction "SHIELD_S2") (pintype "passive"))
      (node (ref "J2") (pin "1") (pinfunction "1_1") (pintype "passive"))
      (node (ref "J2") (pin "13") (pinfunction "13_13") (pintype "passive"))
      (node (ref "J2") (pin "14") (pinfunction "14_14") (pintype "passive"))
      (node (ref "J2") (pin "19") (pinfunction "19_19") (pintype "passive"))
      (node (ref "J2") (pin "2") (pinfunction "2_2") (pintype "passive"))
      (node (ref "J2") (pin "20") (pinfunction "20_20") (pintype "passive"))
      (node (ref "J2") (pin "25") (pinfunction "25_25") (pintype "passive"))
      (node (ref "J2") (pin "26") (pinfunction "26_26") (pintype "passive"))
      (node (ref "J2") (pin "31") (pinfunction "31_31") (pintype "passive"))
      (node (ref "J2") (pin "32") (pinfunction "32_32") (pintype "passive"))
      (node (ref "J2") (pin "37") (pinfunction "37_37") (pintype "passive"))
      (node (ref "J2") (pin "38") (pinfunction "38_38") (pintype "passive"))
      (node (ref "J2") (pin "43") (pinfunction "43_43") (pintype "passive"))
      (node (ref "J2") (pin "44") (pinfunction "44_44") (pintype "passive"))
      (node (ref "J2") (pin "49") (pinfunction "49_49") (pintype "passive"))
      (node (ref "J2") (pin "50") (pinfunction "50_50") (pintype "passive"))
      (node (ref "J2") (pin "55") (pinfunction "55_55") (pintype "passive"))
      (node (ref "J2") (pin "56") (pinfunction "56_56") (pintype "passive"))
      (node (ref "J2") (pin "59") (pinfunction "59_59") (pintype "passive"))
      (node (ref "J2") (pin "60") (pinfunction "60_60") (pintype "passive"))
      (node (ref "J2") (pin "7") (pinfunction "7_7") (pintype "passive"))
      (node (ref "J2") (pin "8") (pinfunction "8_8") (pintype "passive"))
      (node (ref "J2") (pin "S1") (pinfunction "SHIELD_S1") (pintype "passive"))
      (node (ref "J2") (pin "S2") (pinfunction "SHIELD_S2") (pintype "passive"))
      (node (ref "JTAG") (pin "2") (pinfunction "2_2") (pintype "passive"))
      (node (ref "R12") (pin "1") (pinfunction "1_1") (pintype "passive"))
      (node (ref "R14") (pin "1") (pinfunction "1_1") (pintype "passive"))
      (node (ref "R20") (pin "1") (pinfunction "1_1") (pintype "passive"))
      (node (ref "R23") (pin "1") (pinfunction "1_1") (pintype "passive"))
      (node (ref "R26") (pin "1") (pinfunction "1_1") (pintype "passive"))
      (node (ref "R4") (pin "2") (pinfunction "2_2") (pintype "passive"))
      (node (ref "R5") (pin "2") (pinfunction "2_2") (pintype "passive"))
      (node (ref "U1") (pin "A1") (pinfunction "GND_A1") (pintype "power_in"))
      (node (ref "U1") (pin "A11") (pinfunction "GND_A11") (pintype "power_in"))
      (node (ref "U1") (pin "A14") (pinfunction "GND_A14") (pintype "power_in"))
      (node (ref "U1") (pin "A6") (pinfunction "GND_A6") (pintype "power_in"))
      (node (ref "U1") (pin "A9") (pinfunction "GND_A9") (pintype "power_in"))
      (node (ref "U1") (pin "B4") (pinfunction "GND_B4") (pintype "power_in"))
      (node (ref "U1") (pin "B7") (pinfunction "GND_B7") (pintype "power_in"))
      (node (ref "U1") (pin "B9") (pinfunction "GND_B9") (pintype "power_in"))
      (node (ref "U1") (pin "C13") (pinfunction "GND_C13") (pintype "power_in"))
      (node (ref "U1") (pin "C2") (pinfunction "GND_C2") (pintype "power_in"))
      (node (ref "U1") (pin "C6") (pinfunction "GND_C6") (pintype "power_in"))
      (node (ref "U1") (pin "C7") (pinfunction "GND_C7") (pintype "power_in"))
      (node (ref "U1") (pin "C8") (pinfunction "GND_C8") (pintype "power_in"))
      (node (ref "U1") (pin "C9") (pinfunction "GND_C9") (pintype "power_in"))
      (node (ref "U1") (pin "D11") (pinfunction "GND_D11") (pintype "power_in"))
      (node (ref "U1") (pin "D5") (pinfunction "GND_D5") (pintype "power_in"))
      (node (ref "U1") (pin "D7") (pinfunction "GND_D7") (pintype "power_in"))
      (node (ref "U1") (pin "D9") (pinfunction "GND_D9") (pintype "power_in"))
      (node (ref "U1") (pin "E1") (pinfunction "GND_E1") (pintype "power_in"))
      (node (ref "U1") (pin "E10") (pinfunction "GND_E10") (pintype "power_in"))
      (node (ref "U1") (pin "E14") (pinfunction "GND_E14") (pintype "power_in"))
      (node (ref "U1") (pin "E3") (pinfunction "GND_E3") (pintype "power_in"))
      (node (ref "U1") (pin "E6") (pinfunction "GND_E6") (pintype "power_in"))
      (node (ref "U1") (pin "E8") (pinfunction "GND_E8") (pintype "power_in"))
      (node (ref "U1") (pin "F5") (pinfunction "GND_F5") (pintype "power_in"))
      (node (ref "U1") (pin "F7") (pinfunction "NC_F7") (pintype "bidirectional"))
      (node (ref "U1") (pin "F9") (pinfunction "GND_F9") (pintype "power_in"))
      (node (ref "U1") (pin "G10") (pinfunction "GND_G10") (pintype "power_in"))
      (node (ref "U1") (pin "G12") (pinfunction "GND_G12") (pintype "power_in"))
      (node (ref "U1") (pin "G3") (pinfunction "GND_G3") (pintype "power_in"))
      (node (ref "U1") (pin "G6") (pinfunction "GND_G6") (pintype "power_in"))
      (node (ref "U1") (pin "G7") (pinfunction "NC_G7") (pintype "bidirectional"))
      (node (ref "U1") (pin "G8") (pinfunction "NC_G8") (pintype "bidirectional"))
      (node (ref "U1") (pin "H5") (pinfunction "GND_H5") (pintype "power_in"))
      (node (ref "U1") (pin "H7") (pinfunction "NC_H7") (pintype "bidirectional"))
      (node (ref "U1") (pin "H8") (pinfunction "NC_H8") (pintype "bidirectional"))
      (node (ref "U1") (pin "H9") (pinfunction "GND_H9") (pintype "power_in"))
      (node (ref "U1") (pin "J10") (pinfunction "GND_J10") (pintype "power_in"))
      (node (ref "U1") (pin "J6") (pinfunction "GND_J6") (pintype "power_in"))
      (node (ref "U1") (pin "J7") (pinfunction "DXN_0_J7") (pintype "bidirectional"))
      (node (ref "U1") (pin "J8") (pinfunction "DXP_0_J8") (pintype "bidirectional"))
      (node (ref "U1") (pin "K1") (pinfunction "GND_K1") (pintype "power_in"))
      (node (ref "U1") (pin "K14") (pinfunction "GND_K14") (pintype "power_in"))
      (node (ref "U1") (pin "K5") (pinfunction "GND_K5") (pintype "power_in"))
      (node (ref "U1") (pin "K7") (pinfunction "GND_K7") (pintype "power_in"))
      (node (ref "U1") (pin "K9") (pinfunction "GND_K9") (pintype "power_in"))
      (node (ref "U1") (pin "L10") (pinfunction "GND_L10") (pintype "power_in"))
      (node (ref "U1") (pin "L11") (pinfunction "GND_L11") (pintype "power_in"))
      (node (ref "U1") (pin "L4") (pinfunction "GND_L4") (pintype "power_in"))
      (node (ref "U1") (pin "L6") (pinfunction "GND_L6") (pintype "power_in"))
      (node (ref "U1") (pin "L8") (pinfunction "GND_L8") (pintype "power_in"))
      (node (ref "U1") (pin "N12") (pinfunction "GND_N12") (pintype "power_in"))
      (node (ref "U1") (pin "N3") (pinfunction "GND_N3") (pintype "power_in"))
      (node (ref "U1") (pin "N5") (pinfunction "GND_N5") (pintype "power_in"))
      (node (ref "U1") (pin "N9") (pinfunction "GND_N9") (pintype "power_in"))
      (node (ref "U1") (pin "P1") (pinfunction "GND_P1") (pintype "power_in"))
      (node (ref "U1") (pin "P14") (pinfunction "GND_P14") (pintype "power_in"))
      (node (ref "U2") (pin "4") (pinfunction "VSS_4") (pintype "bidirectional"))
      (node (ref "U3") (pin "1") (pinfunction "GND_1") (pintype "bidirectional"))
      (node (ref "U4") (pin "1") (pinfunction "GND_1") (pintype "bidirectional"))
      (node (ref "U5") (pin "1") (pinfunction "GND_1") (pintype "bidirectional"))
      (node (ref "U6") (pin "1") (pinfunction "GND_1") (pintype "bidirectional"))
      (node (ref "X1") (pin "2") (pinfunction "GND_2") (pintype "power_in"))
    )
    (net (code "76") (name "H3") (class "Default")
      (node (ref "J1") (pin "41") (pinfunction "41_41") (pintype "passive"))
      (node (ref "U1") (pin "H3") (pinfunction "IO_L13N_T2_MRCC_34_H3") (pintype "bidirectional"))
    )
    (net (code "77") (name "H4") (class "Default")
      (node (ref "J1") (pin "43") (pinfunction "43_43") (pintype "passive"))
      (node (ref "U1") (pin "H4") (pinfunction "IO_L13P_T2_MRCC_34_H4") (pintype "bidirectional"))
    )
    (net (code "78") (name "INIT") (class "Default")
      (node (ref "R6") (pin "1") (pinfunction "1_1") (pintype "passive"))
      (node (ref "U1") (pin "P8") (pinfunction "INIT_B_0_P8") (pintype "bidirectional"))
    )
    (net (code "79") (name "J1") (class "Default")
      (node (ref "J1") (pin "47") (pinfunction "47_47") (pintype "passive"))
      (node (ref "U1") (pin "J1") (pinfunction "IO_L15N_T2_DQS_34_J1") (pintype "bidirectional"))
    )
    (net (code "80") (name "J2") (class "Default")
      (node (ref "J1") (pin "49") (pinfunction "49_49") (pintype "passive"))
      (node (ref "U1") (pin "J2") (pinfunction "IO_L15P_T2_DQS_34_J2") (pintype "bidirectional"))
    )
    (net (code "81") (name "J3") (class "Default")
      (node (ref "J1") (pin "48") (pinfunction "48_48") (pintype "passive"))
      (node (ref "U1") (pin "J3") (pinfunction "IO_L17N_T2_34_J3") (pintype "bidirectional"))
    )
    (net (code "82") (name "J4") (class "Default")
      (node (ref "J1") (pin "50") (pinfunction "50_50") (pintype "passive"))
      (node (ref "U1") (pin "J4") (pinfunction "IO_L17P_T2_34_J4") (pintype "bidirectional"))
    )
    (net (code "83") (name "K3") (class "Default")
      (node (ref "J1") (pin "54") (pinfunction "54_54") (pintype "passive"))
      (node (ref "U1") (pin "K3") (pinfunction "IO_L16N_T2_34_K3") (pintype "bidirectional"))
    )
    (net (code "84") (name "K4") (class "Default")
      (node (ref "J1") (pin "56") (pinfunction "56_56") (pintype "passive"))
      (node (ref "U1") (pin "K4") (pinfunction "IO_L16P_T2_34_K4") (pintype "bidirectional"))
    )
    (net (code "85") (name "L1") (class "Default")
      (node (ref "J1") (pin "53") (pinfunction "53_53") (pintype "passive"))
      (node (ref "U1") (pin "L1") (pinfunction "IO_L18N_T2_34_L1") (pintype "bidirectional"))
    )
    (net (code "86") (name "L2") (class "Default")
      (node (ref "J1") (pin "59") (pinfunction "59_59") (pintype "passive"))
      (node (ref "U1") (pin "L2") (pinfunction "IO_L22N_T3_34_L2") (pintype "bidirectional"))
    )
    (net (code "87") (name "L3") (class "Default")
      (node (ref "J1") (pin "61") (pinfunction "61_61") (pintype "passive"))
      (node (ref "U1") (pin "L3") (pinfunction "IO_L22P_T3_34_L3") (pintype "bidirectional"))
    )
    (net (code "88") (name "LED") (class "Default")
      (node (ref "LED") (pin "A") (pinfunction "A_A") (pintype "passive"))
      (node (ref "U1") (pin "M10") (pinfunction "IO_25_14_M10") (pintype "bidirectional"))
    )
    (net (code "89") (name "M0_0") (class "Default")
      (node (ref "R16") (pin "2") (pinfunction "2_2") (pintype "passive"))
      (node (ref "U1") (pin "M7") (pinfunction "M0_0_M7") (pintype "bidirectional"))
    )
    (net (code "90") (name "M1") (class "Default")
      (node (ref "J1") (pin "55") (pinfunction "55_55") (pintype "passive"))
      (node (ref "U1") (pin "M1") (pinfunction "IO_L18P_T2_34_M1") (pintype "bidirectional"))
    )
    (net (code "91") (name "M1_0") (class "Default")
      (node (ref "R5") (pin "1") (pinfunction "1_1") (pintype "passive"))
      (node (ref "U1") (pin "M8") (pinfunction "M1_0_M8") (pintype "bidirectional"))
    )
    (net (code "92") (name "M2") (class "Default")
      (node (ref "J1") (pin "60") (pinfunction "60_60") (pintype "passive"))
      (node (ref "U1") (pin "M2") (pinfunction "IO_L19N_T3_VREF_34_M2") (pintype "bidirectional"))
    )
    (net (code "93") (name "M2_0") (class "Default")
      (node (ref "R4") (pin "1") (pinfunction "1_1") (pintype "passive"))
      (node (ref "U1") (pin "M9") (pinfunction "M2_0_M9") (pintype "bidirectional"))
    )
    (net (code "94") (name "M3") (class "Default")
      (node (ref "J1") (pin "62") (pinfunction "62_62") (pintype "passive"))
      (node (ref "U1") (pin "M3") (pinfunction "IO_L19P_T3_34_M3") (pintype "bidirectional"))
    )
    (net (code "95") (name "N1") (class "Default")
      (node (ref "J1") (pin "65") (pinfunction "65_65") (pintype "passive"))
      (node (ref "U1") (pin "N1") (pinfunction "IO_L20N_T3_34_N1") (pintype "bidirectional"))
    )
    (net (code "96") (name "Net-(DONE-PadC)") (class "Default")
      (node (ref "DONE") (pin "C") (pinfunction "C_C") (pintype "passive"))
      (node (ref "R24") (pin "2") (pinfunction "2_2") (pintype "passive"))
    )
    (net (code "97") (name "Net-(JTAG-Pad3)") (class "Default")
      (node (ref "JTAG") (pin "3") (pinfunction "3_3") (pintype "passive"))
      (node (ref "R21") (pin "1") (pinfunction "1_1") (pintype "passive"))
    )
    (net (code "98") (name "Net-(JTAG-Pad5)") (class "Default")
      (node (ref "JTAG") (pin "5") (pinfunction "5_5") (pintype "passive"))
      (node (ref "R18") (pin "1") (pinfunction "1_1") (pintype "passive"))
    )
    (net (code "99") (name "Net-(JTAG-Pad6)") (class "Default")
      (node (ref "JTAG") (pin "6") (pinfunction "6_6") (pintype "passive"))
      (node (ref "R15") (pin "1") (pinfunction "1_1") (pintype "passive"))
    )
    (net (code "100") (name "Net-(L3-Pad1)") (class "Default")
      (node (ref "L3") (pin "1") (pinfunction "1_1") (pintype "passive"))
      (node (ref "U1") (pin "F8") (pinfunction "NC_F8") (pintype "bidirectional"))
    )
    (net (code "101") (name "Net-(LED-PadC)") (class "Default")
      (node (ref "LED") (pin "C") (pinfunction "C_C") (pintype "passive"))
      (node (ref "R12") (pin "2") (pinfunction "2_2") (pintype "passive"))
    )
    (net (code "102") (name "Net-(U1A-CFGBVS_0)") (class "Default")
      (node (ref "R7") (pin "2") (pinfunction "2_2") (pintype "passive"))
      (node (ref "U1") (pin "N7") (pinfunction "CFGBVS_0_N7") (pintype "bidirectional"))
    )
    (net (code "103") (name "Net-(U1C-IO_L24N_T3_34)") (class "Default")
      (node (ref "N4") (pin "TP") (pinfunction "TP_TP") (pintype "input"))
      (node (ref "U1") (pin "N4") (pinfunction "IO_L24N_T3_34_N4") (pintype "bidirectional"))
    )
    (net (code "104") (name "Net-(U1C-IO_L24P_T3_34)") (class "Default")
      (node (ref "P5") (pin "TP") (pinfunction "TP_TP") (pintype "input"))
      (node (ref "U1") (pin "P5") (pinfunction "IO_L24P_T3_34_P5") (pintype "bidirectional"))
    )
    (net (code "105") (name "Net-(U2-IO3{slash}RESET#)") (class "Default")
      (node (ref "R1") (pin "2") (pinfunction "2_2") (pintype "passive"))
      (node (ref "R2") (pin "1") (pinfunction "1_1") (pintype "passive"))
      (node (ref "U2") (pin "7") (pinfunction "IO3/RESET#_7") (pintype "bidirectional"))
    )
    (net (code "106") (name "Net-(U2-SI{slash}IO0)") (class "Default")
      (node (ref "R3") (pin "2") (pinfunction "2_2") (pintype "passive"))
      (node (ref "U2") (pin "5") (pinfunction "SI/IO0_5") (pintype "bidirectional"))
    )
    (net (code "107") (name "Net-(U2-SO{slash}IO1)") (class "Default")
      (node (ref "R9") (pin "1") (pinfunction "1_1") (pintype "passive"))
      (node (ref "U2") (pin "2") (pinfunction "SO/IO1_2") (pintype "bidirectional"))
    )
    (net (code "108") (name "Net-(U2-WP#{slash}IO2)") (class "Default")
      (node (ref "R10") (pin "1") (pinfunction "1_1") (pintype "passive"))
      (node (ref "R11") (pin "1") (pinfunction "1_1") (pintype "passive"))
      (node (ref "U2") (pin "3") (pinfunction "WP#/IO2_3") (pintype "bidirectional"))
    )
    (net (code "109") (name "Net-(U3-FB)") (class "Default")
      (node (ref "R13") (pin "2") (pinfunction "2_2") (pintype "passive"))
      (node (ref "R14") (pin "2") (pinfunction "2_2") (pintype "passive"))
      (node (ref "U3") (pin "5") (pinfunction "FB_5") (pintype "bidirectional"))
    )
    (net (code "110") (name "Net-(U3-SW)") (class "Default")
      (node (ref "L1") (pin "2") (pinfunction "2_2") (pintype "passive"))
      (node (ref "U3") (pin "2") (pinfunction "SW_2") (pintype "bidirectional"))
    )
    (net (code "111") (name "Net-(U4-FB)") (class "Default")
      (node (ref "R19") (pin "2") (pinfunction "2_2") (pintype "passive"))
      (node (ref "R20") (pin "2") (pinfunction "2_2") (pintype "passive"))
      (node (ref "U4") (pin "5") (pinfunction "FB_5") (pintype "bidirectional"))
    )
    (net (code "112") (name "Net-(U4-SW)") (class "Default")
      (node (ref "L2") (pin "2") (pinfunction "2_2") (pintype "passive"))
      (node (ref "U4") (pin "2") (pinfunction "SW_2") (pintype "bidirectional"))
    )
    (net (code "113") (name "Net-(U5-FB)") (class "Default")
      (node (ref "R22") (pin "2") (pinfunction "2_2") (pintype "passive"))
      (node (ref "R23") (pin "2") (pinfunction "2_2") (pintype "passive"))
      (node (ref "U5") (pin "5") (pinfunction "FB_5") (pintype "bidirectional"))
    )
    (net (code "114") (name "Net-(U5-SW)") (class "Default")
      (node (ref "L4") (pin "2") (pinfunction "2_2") (pintype "passive"))
      (node (ref "U5") (pin "2") (pinfunction "SW_2") (pintype "bidirectional"))
    )
    (net (code "115") (name "Net-(U6-FB)") (class "Default")
      (node (ref "R26") (pin "2") (pinfunction "2_2") (pintype "passive"))
      (node (ref "R27") (pin "2") (pinfunction "2_2") (pintype "passive"))
      (node (ref "U6") (pin "5") (pinfunction "FB_5") (pintype "bidirectional"))
    )
    (net (code "116") (name "Net-(U6-SW)") (class "Default")
      (node (ref "L5") (pin "2") (pinfunction "2_2") (pintype "passive"))
      (node (ref "U6") (pin "2") (pinfunction "SW_2") (pintype "bidirectional"))
    )
    (net (code "117") (name "P2") (class "Default")
      (node (ref "J1") (pin "67") (pinfunction "67_67") (pintype "passive"))
      (node (ref "U1") (pin "P2") (pinfunction "IO_L20P_T3_34_P2") (pintype "bidirectional"))
    )
    (net (code "118") (name "P3") (class "Default")
      (node (ref "J1") (pin "66") (pinfunction "66_66") (pintype "passive"))
      (node (ref "U1") (pin "P3") (pinfunction "IO_L21N_T3_DQS_34_P3") (pintype "bidirectional"))
    )
    (net (code "119") (name "P4") (class "Default")
      (node (ref "J1") (pin "68") (pinfunction "68_68") (pintype "passive"))
      (node (ref "U1") (pin "P4") (pinfunction "IO_L21P_T3_DQS_34_P4") (pintype "bidirectional"))
    )
    (net (code "120") (name "PROG") (class "Default")
      (node (ref "R17") (pin "2") (pinfunction "2_2") (pintype "passive"))
      (node (ref "U1") (pin "L7") (pinfunction "PROGRAM_B_0_L7") (pintype "bidirectional"))
    )
    (net (code "121") (name "PROG_DONE") (class "Default")
      (node (ref "R24") (pin "1") (pinfunction "1_1") (pintype "passive"))
      (node (ref "R25") (pin "1") (pinfunction "1_1") (pintype "passive"))
      (node (ref "U1") (pin "P9") (pinfunction "DONE_0_P9") (pintype "bidirectional"))
    )
    (net (code "122") (name "TCK") (class "Default")
      (node (ref "R21") (pin "2") (pinfunction "2_2") (pintype "passive"))
      (node (ref "U1") (pin "A7") (pinfunction "TCK_0_A7") (pintype "bidirectional"))
    )
    (net (code "123") (name "TDI") (class "Default")
      (node (ref "R18") (pin "2") (pinfunction "2_2") (pintype "passive"))
      (node (ref "U1") (pin "P7") (pinfunction "TDI_0_P7") (pintype "bidirectional"))
    )
    (net (code "124") (name "TDO") (class "Default")
      (node (ref "JTAG") (pin "4") (pinfunction "4_4") (pintype "passive"))
      (node (ref "U1") (pin "P6") (pinfunction "TDO_0_P6") (pintype "bidirectional"))
    )
    (net (code "125") (name "TMS") (class "Default")
      (node (ref "R15") (pin "2") (pinfunction "2_2") (pintype "passive"))
      (node (ref "U1") (pin "M6") (pinfunction "TMS_0_M6") (pintype "bidirectional"))
    )
    (net (code "126") (name "UART_CTS") (class "Default")
      (node (ref "J2") (pin "63") (pinfunction "63_63") (pintype "passive"))
      (node (ref "U1") (pin "A10") (pinfunction "IO_L3N_T0_DQS_EMCCLK_14_A10") (pintype "bidirectional"))
    )
    (net (code "127") (name "UART_RTS") (class "Default")
      (node (ref "J2") (pin "61") (pinfunction "61_61") (pintype "passive"))
      (node (ref "U1") (pin "B10") (pinfunction "IO_L3P_T0_DQS_PUDC_B_14_B10") (pintype "bidirectional"))
    )
    (net (code "128") (name "UART_RX") (class "Default")
      (node (ref "J2") (pin "62") (pinfunction "62_62") (pintype "passive"))
      (node (ref "U1") (pin "A13") (pinfunction "IO_L4N_T0_D05_14_A13") (pintype "bidirectional"))
    )
    (net (code "129") (name "UART_TX") (class "Default")
      (node (ref "J2") (pin "64") (pinfunction "64_64") (pintype "passive"))
      (node (ref "U1") (pin "A12") (pinfunction "IO_L4P_T0_D04_14_A12") (pintype "bidirectional"))
    )
    (net (code "130") (name "VIO_34") (class "Default")
      (node (ref "B34") (pin "2") (pinfunction "2_2") (pintype "passive"))
      (node (ref "C10") (pin "2") (pinfunction "2_2") (pintype "passive"))
      (node (ref "C11") (pin "2") (pinfunction "2_2") (pintype "passive"))
      (node (ref "C14") (pin "2") (pinfunction "2_2") (pintype "passive"))
      (node (ref "C9") (pin "2") (pinfunction "2_2") (pintype "passive"))
      (node (ref "U1") (pin "G2") (pinfunction "VCCO_34_G2") (pintype "bidirectional"))
      (node (ref "U1") (pin "K2") (pinfunction "VCCO_34_K2") (pintype "bidirectional"))
      (node (ref "U1") (pin "N2") (pinfunction "VCCO_34_N2") (pintype "bidirectional"))
    )
    (net (code "131") (name "unconnected-(U1B-IO_L12N_T1_MRCC_14-PadF11)") (class "Default")
      (node (ref "U1") (pin "F11") (pinfunction "IO_L12N_T1_MRCC_14_F11") (pintype "bidirectional"))
    )
    (net (code "132") (name "unconnected-(U1C-IO_25_34-PadL5)") (class "Default")
      (node (ref "U1") (pin "L5") (pinfunction "IO_25_34_L5") (pintype "bidirectional"))
    )
    (net (code "133") (name "unconnected-(U1C-IO_L1P_T0_34-PadD3)") (class "Default")
      (node (ref "U1") (pin "D3") (pinfunction "IO_L1P_T0_34_D3") (pintype "bidirectional"))
    )
    (net (code "134") (name "unconnected-(U1C-IO_L14N_T2_SRCC_34-PadH1)") (class "Default")
      (node (ref "U1") (pin "H1") (pinfunction "IO_L14N_T2_SRCC_34_H1") (pintype "bidirectional"))
    )
    (net (code "135") (name "unconnected-(U1C-IO_L14P_T2_SRCC_34-PadH2)") (class "Default")
      (node (ref "U1") (pin "H2") (pinfunction "IO_L14P_T2_SRCC_34_H2") (pintype "bidirectional"))
    )
    (net (code "136") (name "unconnected-(U1C-IO_L23N_T3_34-PadM4)") (class "Default")
      (node (ref "U1") (pin "M4") (pinfunction "IO_L23N_T3_34_M4") (pintype "bidirectional"))
    )
    (net (code "137") (name "unconnected-(U1C-IO_L23P_T3_34-PadM5)") (class "Default")
      (node (ref "U1") (pin "M5") (pinfunction "IO_L23P_T3_34_M5") (pintype "bidirectional"))
    )
    (net (code "138") (name "unconnected-(U3-PG-Pad6)") (class "Default")
      (node (ref "U3") (pin "6") (pinfunction "PG_6") (pintype "bidirectional"))
    )
    (net (code "139") (name "unconnected-(U4-PG-Pad6)") (class "Default")
      (node (ref "U4") (pin "6") (pinfunction "PG_6") (pintype "bidirectional"))
    )
    (net (code "140") (name "unconnected-(U5-PG-Pad6)") (class "Default")
      (node (ref "U5") (pin "6") (pinfunction "PG_6") (pintype "bidirectional"))
    )
    (net (code "141") (name "unconnected-(U6-PG-Pad6)") (class "Default")
      (node (ref "U6") (pin "6") (pinfunction "PG_6") (pintype "bidirectional"))
    )
    (net (code "142") (name "unconnected-(X1-TRI-Pad1)") (class "Default")
      (node (ref "X1") (pin "1") (pinfunction "TRI_1") (pintype "input"))
    )
  )
)
